# musIR-tiny-mk-1_0_2.net
KiCad netlist of a schematic drawn in EAGLE
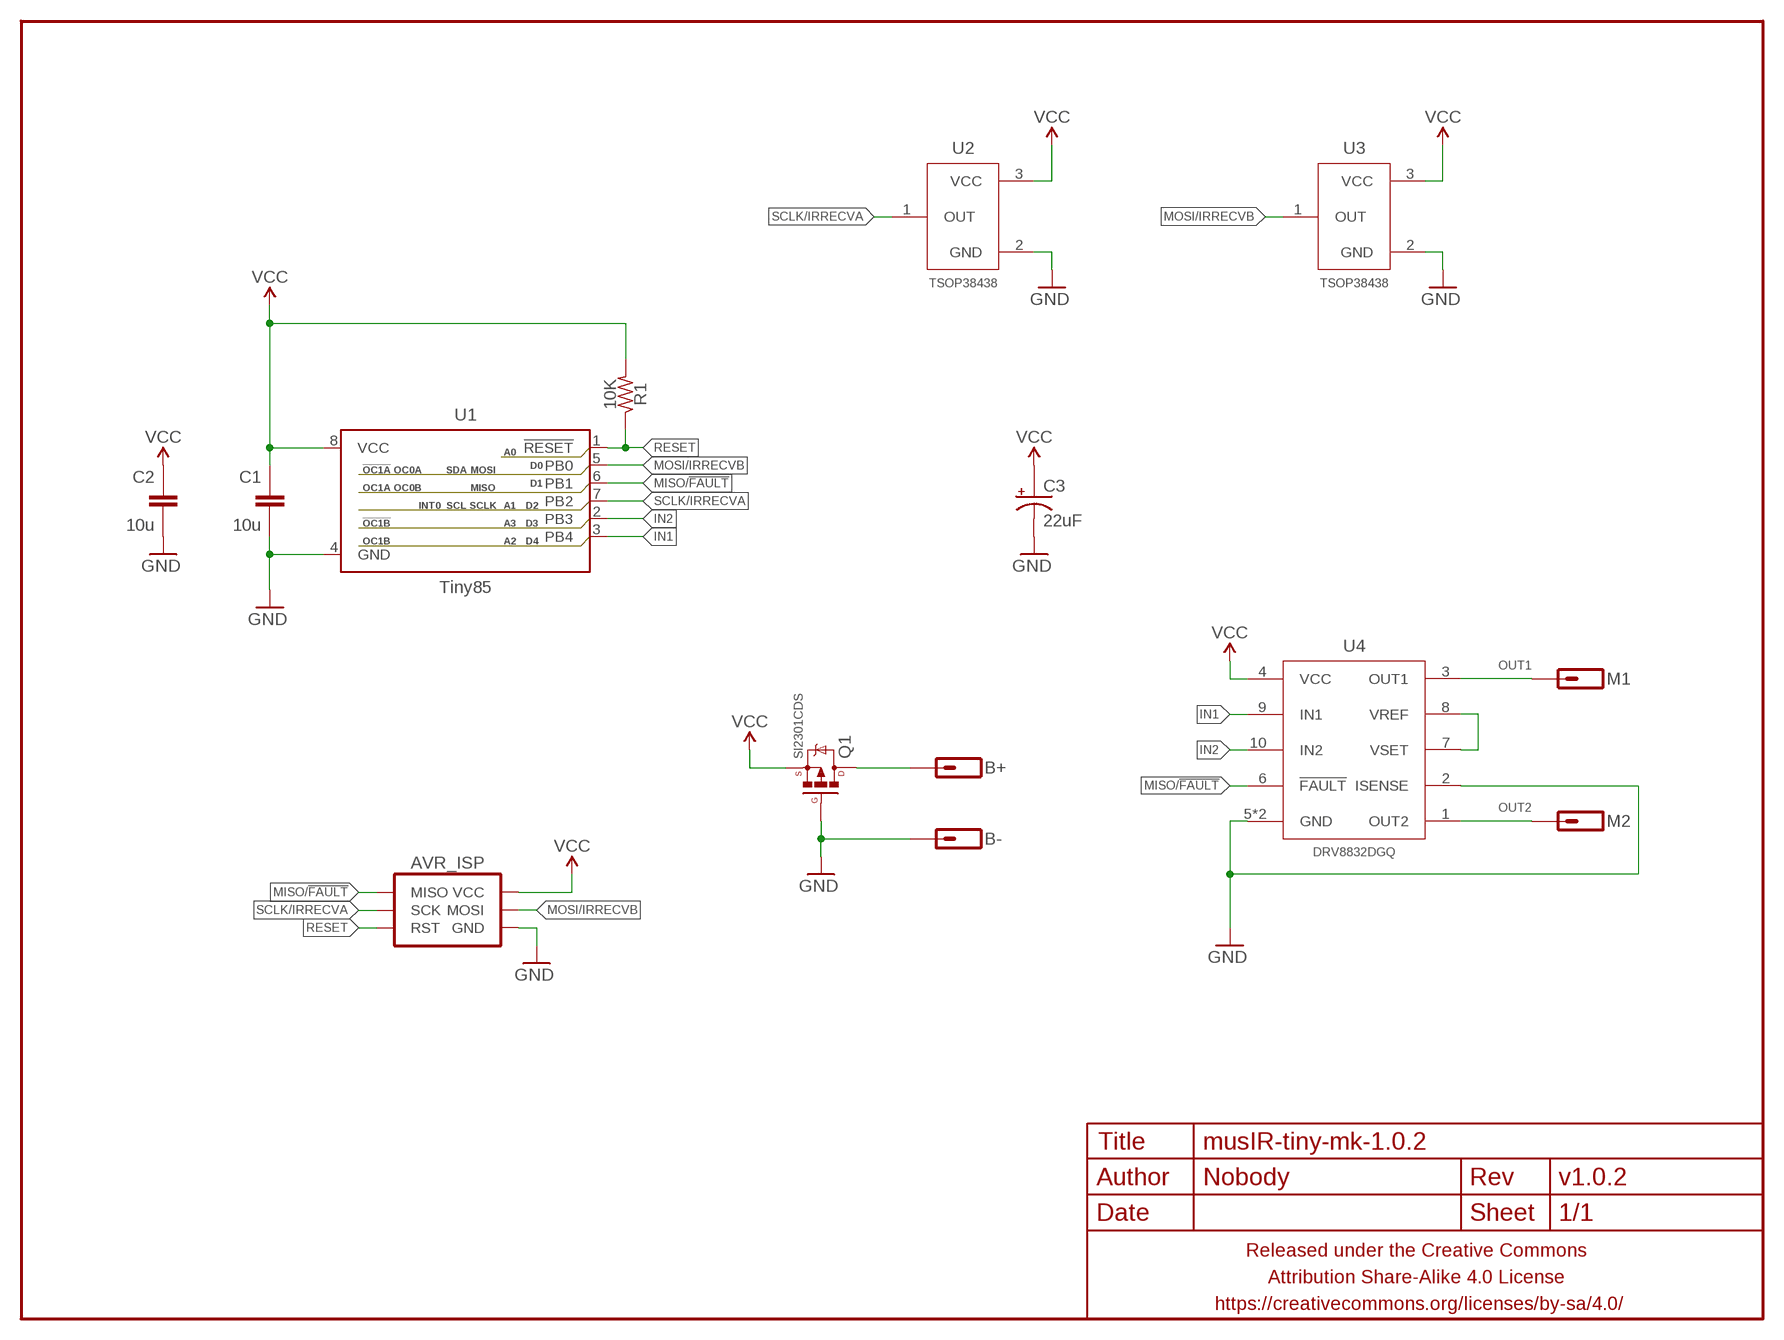
[diagram p0: schematic, sheet 1]

(export (version "E")
  (design (tool "Eeschema 10.0.6"))
  (components
    (comp (ref "AVR_ISP")
      (value "AVR_SPI_PRG_6TESTPOINTS")
      (footprint "eagle-import:2X3_TEST_POINTS")
      (libsource (lib "eagle-import") (part "AVR_SPI_PRG_6TESTPOINTS"))
    )
    (comp (ref "B+")
      (value "M01PTH")
      (footprint "eagle-import:1X01")
      (libsource (lib "eagle-import") (part "M01PTH"))
    )
    (comp (ref "B-")
      (value "M01PTH")
      (footprint "eagle-import:1X01")
      (libsource (lib "eagle-import") (part "M01PTH"))
    )
    (comp (ref "C1")
      (value "10u")
      (footprint "eagle-import:C0805-TIGHTER")
      (libsource (lib "eagle-import") (part "CAPACITOR-CERAMICC0805-TIGHTER"))
    )
    (comp (ref "C2")
      (value "10u")
      (footprint "eagle-import:C0805-TIGHTER")
      (libsource (lib "eagle-import") (part "CAPACITOR-CERAMICC0805-TIGHTER"))
    )
    (comp (ref "C3")
      (value "22uF")
      (footprint "eagle-import:C_6032-28R")
      (libsource (lib "eagle-import") (part "CAPACITOR-POLARIZEDC/6032-28R"))
    )
    (comp (ref "FRAME1")
      (value "FRAME-LETTERNO_PACKAGE")
      (footprint "eagle-import:DUMMY")
      (fields (field (name "VERSION") "v1.0.2") (field (name "DESIGNER") "Nobody"))
      (libsource (lib "eagle-import") (part "FRAME-LETTERNO_PACKAGE"))
    )
    (comp (ref "M1")
      (value "M01PTH")
      (footprint "eagle-import:1X01")
      (libsource (lib "eagle-import") (part "M01PTH"))
    )
    (comp (ref "M2")
      (value "M01PTH")
      (footprint "eagle-import:1X01")
      (libsource (lib "eagle-import") (part "M01PTH"))
    )
    (comp (ref "Q1")
      (value "SI2301CDS")
      (footprint "eagle-import:SOT23")
      (libsource (lib "eagle-import") (part "MOSFET-PCHANNELSOT-23"))
    )
    (comp (ref "R1")
      (value "10K")
      (footprint "eagle-import:R0603-TIGHTER")
      (libsource (lib "eagle-import") (part "RESISTORR0603-TIGHTER"))
    )
    (comp (ref "U1")
      (value "Tiny85")
      (footprint "eagle-import:SO08-EIAJ")
      (libsource (lib "eagle-import") (part "ATTINY45TINY85-20-SOICW"))
    )
    (comp (ref "U2")
      (value "TSOP38438")
      (footprint "eagle-import:TSOP38238")
      (libsource (lib "eagle-import") (part "TSOP382__/4__"))
    )
    (comp (ref "U3")
      (value "TSOP38438")
      (footprint "eagle-import:TSOP38238")
      (libsource (lib "eagle-import") (part "TSOP382__/4__"))
    )
    (comp (ref "U4")
      (value "DRV8832DGQ")
      (footprint "eagle-import:MSOP-10-PAD")
      (libsource (lib "eagle-import") (part "DRV8832DGQ"))
    )
  )
  (nets
    (net (code "1") (name "/MISO{slash}~{FAULT}") (class "Default")
      (node (ref "AVR_ISP") (pin "1") (pinfunction "MISO_1") (pintype "passive"))
      (node (ref "U1") (pin "6") (pinfunction "PB1_6") (pintype "bidirectional"))
      (node (ref "U4") (pin "6") (pinfunction "~{FAULT}_6") (pintype "bidirectional"))
    )
    (net (code "2") (name "/OUT1") (class "Default")
      (node (ref "M1") (pin "1") (pinfunction "1_1") (pintype "passive"))
      (node (ref "U4") (pin "3") (pinfunction "OUT1_3") (pintype "bidirectional"))
    )
    (net (code "3") (name "/OUT2") (class "Default")
      (node (ref "M2") (pin "1") (pinfunction "1_1") (pintype "passive"))
      (node (ref "U4") (pin "1") (pinfunction "OUT2_1") (pintype "bidirectional"))
    )
    (net (code "4") (name "GND") (class "Default")
      (node (ref "AVR_ISP") (pin "6") (pinfunction "GND_6") (pintype "passive"))
      (node (ref "B-") (pin "1") (pinfunction "1_1") (pintype "passive"))
      (node (ref "C1") (pin "2") (pinfunction "2_2") (pintype "passive"))
      (node (ref "C2") (pin "2") (pinfunction "2_2") (pintype "passive"))
      (node (ref "C3") (pin "-") (pinfunction "-_-") (pintype "passive"))
      (node (ref "Q1") (pin "1") (pinfunction "G_1") (pintype "passive"))
      (node (ref "U1") (pin "4") (pinfunction "GND_4") (pintype "bidirectional"))
      (node (ref "U2") (pin "2") (pinfunction "GND_2") (pintype "bidirectional"))
      (node (ref "U3") (pin "2") (pinfunction "GND_2") (pintype "bidirectional"))
      (node (ref "U4") (pin "2") (pinfunction "ISENSE_2") (pintype "bidirectional"))
      (node (ref "U4") (pin "5") (pinfunction "GND_5") (pintype "bidirectional"))
      (node (ref "U4") (pin "PAD") (pinfunction "GND_PAD") (pintype "bidirectional"))
    )
    (net (code "5") (name "IN1") (class "Default")
      (node (ref "U1") (pin "3") (pinfunction "PB4_3") (pintype "bidirectional"))
      (node (ref "U4") (pin "9") (pinfunction "IN1_9") (pintype "bidirectional"))
    )
    (net (code "6") (name "IN2") (class "Default")
      (node (ref "U1") (pin "2") (pinfunction "PB3_2") (pintype "bidirectional"))
      (node (ref "U4") (pin "10") (pinfunction "IN2_10") (pintype "bidirectional"))
    )
    (net (code "7") (name "MOSI{slash}IRRECVB") (class "Default")
      (node (ref "AVR_ISP") (pin "4") (pinfunction "MOSI_4") (pintype "passive"))
      (node (ref "U1") (pin "5") (pinfunction "PB0_5") (pintype "bidirectional"))
      (node (ref "U3") (pin "1") (pinfunction "OUT_1") (pintype "bidirectional"))
    )
    (net (code "8") (name "Net-(Q1-D)") (class "Default")
      (node (ref "B+") (pin "1") (pinfunction "1_1") (pintype "passive"))
      (node (ref "Q1") (pin "3") (pinfunction "D_3") (pintype "passive"))
    )
    (net (code "9") (name "Net-(U4-VREF)") (class "Default")
      (node (ref "U4") (pin "7") (pinfunction "VSET_7") (pintype "bidirectional"))
      (node (ref "U4") (pin "8") (pinfunction "VREF_8") (pintype "bidirectional"))
    )
    (net (code "10") (name "RESET") (class "Default")
      (node (ref "AVR_ISP") (pin "5") (pinfunction "RST_5") (pintype "passive"))
      (node (ref "R1") (pin "1") (pinfunction "1_1") (pintype "passive"))
      (node (ref "U1") (pin "1") (pinfunction "~{RESET}_1") (pintype "bidirectional"))
    )
    (net (code "11") (name "SCLK{slash}IRRECVA") (class "Default")
      (node (ref "AVR_ISP") (pin "3") (pinfunction "SCK_3") (pintype "passive"))
      (node (ref "U1") (pin "7") (pinfunction "PB2_7") (pintype "bidirectional"))
      (node (ref "U2") (pin "1") (pinfunction "OUT_1") (pintype "bidirectional"))
    )
    (net (code "12") (name "VCC") (class "Default")
      (node (ref "AVR_ISP") (pin "2") (pinfunction "VCC_2") (pintype "passive"))
      (node (ref "C1") (pin "1") (pinfunction "1_1") (pintype "passive"))
      (node (ref "C2") (pin "1") (pinfunction "1_1") (pintype "passive"))
      (node (ref "C3") (pin "+") (pinfunction "+_+") (pintype "passive"))
      (node (ref "Q1") (pin "2") (pinfunction "S_2") (pintype "passive"))
      (node (ref "R1") (pin "2") (pinfunction "2_2") (pintype "passive"))
      (node (ref "U1") (pin "8") (pinfunction "VCC_8") (pintype "bidirectional"))
      (node (ref "U2") (pin "3") (pinfunction "VCC_3") (pintype "bidirectional"))
      (node (ref "U3") (pin "3") (pinfunction "VCC_3") (pintype "bidirectional"))
      (node (ref "U4") (pin "4") (pinfunction "VCC_4") (pintype "bidirectional"))
    )
  )
)
